# servo_1.net
KiCad netlist of a schematic drawn in EAGLE
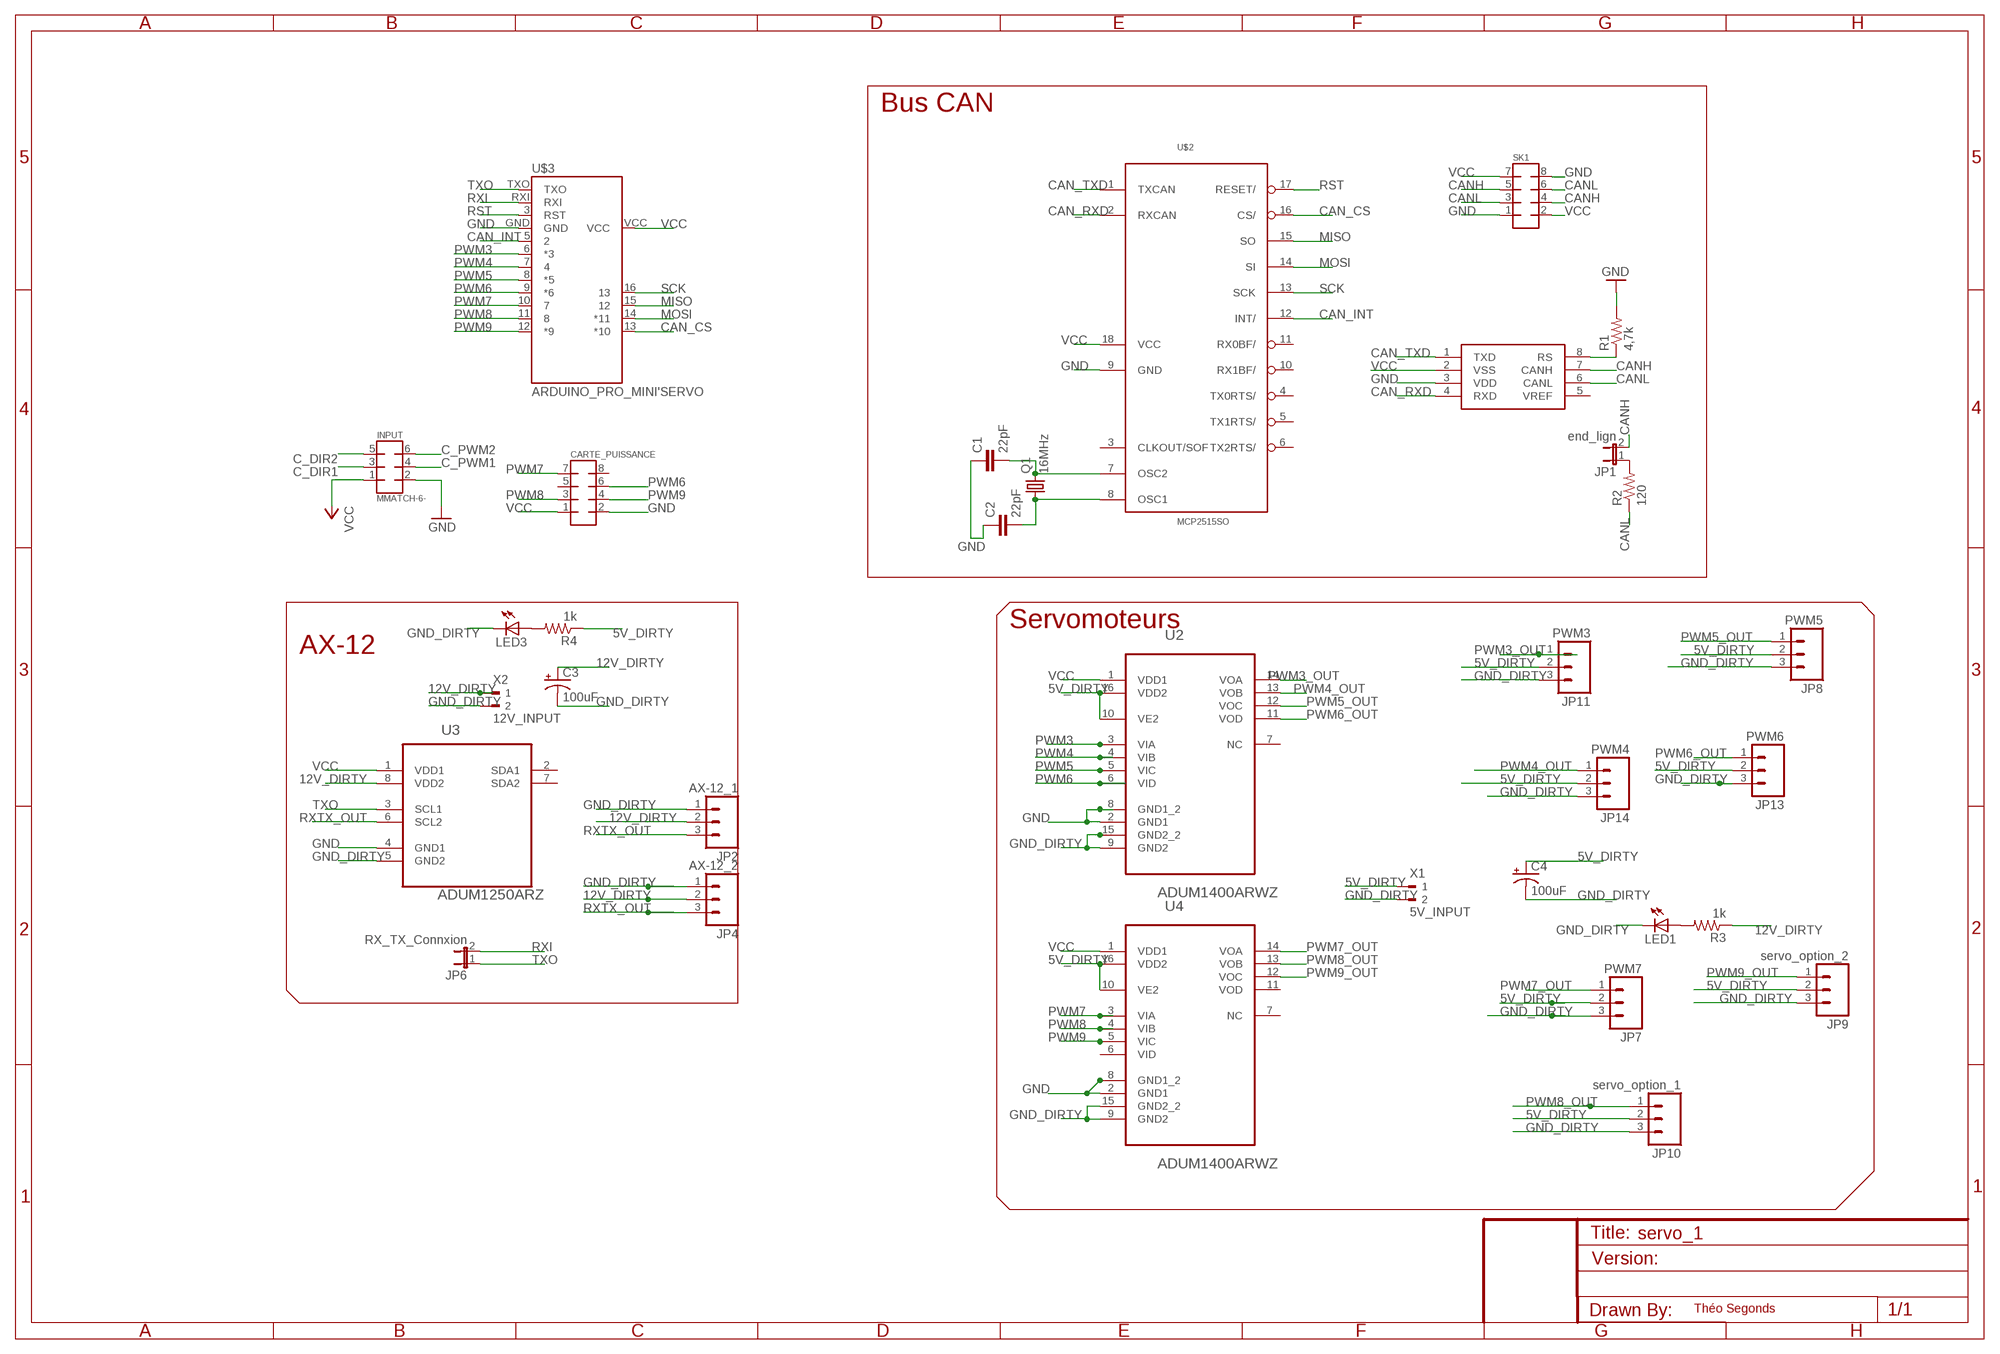
[diagram p0: schematic, sheet 1]

(export (version "E")
  (design (tool "Eeschema 10.0.6"))
  (components
    (comp (ref "C1")
      (value "22pF")
      (footprint "eagle-import:0805")
      (fields (field (name "MF") "AVX") (field (name "MPN") "08055A220JAT2A"))
      (libsource (lib "eagle-import") (part "CAP0805"))
    )
    (comp (ref "C2")
      (value "22pF")
      (footprint "eagle-import:0805")
      (fields (field (name "MF") "AVX") (field (name "MPN") "08055A220JAT2A"))
      (libsource (lib "eagle-import") (part "CAP0805"))
    )
    (comp (ref "C3")
      (value "100uF")
      (footprint "eagle-import:CPOL-RADIAL-100UF-25V")
      (fields (field (name "MF") "RUBYCON") (field (name "MPN") "100TXW100MEFC8X30"))
      (libsource (lib "eagle-import") (part "CAP_POLPTH1"))
    )
    (comp (ref "C4")
      (value "100uF")
      (footprint "eagle-import:CPOL-RADIAL-100UF-25V")
      (fields (field (name "MF") "RUBYCON") (field (name "MPN") "100TXW100MEFC8X30"))
      (libsource (lib "eagle-import") (part "CAP_POLPTH1"))
    )
    (comp (ref "CARTE_PUISSANCE")
      (value "MMATCH-8-PTH")
      (footprint "eagle-import:AMP-215079-8")
      (libsource (lib "eagle-import") (part "MMATCH-8-PTH"))
    )
    (comp (ref "INPUT")
      (value "MMATCH-6-")
      (footprint "eagle-import:AMP-215079-6")
      (libsource (lib "eagle-import") (part "MMATCH-6-"))
    )
    (comp (ref "JP1")
      (value "end_lign")
      (footprint "eagle-import:1X02")
      (libsource (lib "eagle-import") (part "JUMPER-2PTH"))
    )
    (comp (ref "JP2")
      (value "AX-12_1")
      (footprint "eagle-import:MOLEX-1X3")
      (libsource (lib "eagle-import") (part "M03POLAR"))
    )
    (comp (ref "JP4")
      (value "AX-12_2")
      (footprint "eagle-import:MOLEX-1X3")
      (libsource (lib "eagle-import") (part "M03POLAR"))
    )
    (comp (ref "JP6")
      (value "RX_TX_Connxion")
      (footprint "eagle-import:1X02")
      (libsource (lib "eagle-import") (part "JUMPER-2PTH"))
    )
    (comp (ref "JP7")
      (value "PWM7")
      (footprint "eagle-import:1X03")
      (libsource (lib "eagle-import") (part "M03PTH"))
    )
    (comp (ref "JP8")
      (value "PWM5")
      (footprint "eagle-import:1X03")
      (libsource (lib "eagle-import") (part "M03PTH"))
    )
    (comp (ref "JP9")
      (value "servo_option_2")
      (footprint "eagle-import:1X03")
      (libsource (lib "eagle-import") (part "M03PTH"))
    )
    (comp (ref "JP10")
      (value "servo_option_1")
      (footprint "eagle-import:1X03")
      (libsource (lib "eagle-import") (part "M03PTH"))
    )
    (comp (ref "JP11")
      (value "PWM3")
      (footprint "eagle-import:1X03")
      (libsource (lib "eagle-import") (part "M03PTH"))
    )
    (comp (ref "JP13")
      (value "PWM6")
      (footprint "eagle-import:1X03")
      (libsource (lib "eagle-import") (part "M03PTH"))
    )
    (comp (ref "JP14")
      (value "PWM4")
      (footprint "eagle-import:1X03")
      (libsource (lib "eagle-import") (part "M03PTH"))
    )
    (comp (ref "LED1")
      (value "LEDCHIPLED_0805")
      (footprint "eagle-import:CHIPLED_0805")
      (libsource (lib "eagle-import") (part "LEDCHIPLED_0805"))
    )
    (comp (ref "LED3")
      (value "LEDCHIPLED_0805")
      (footprint "eagle-import:CHIPLED_0805")
      (libsource (lib "eagle-import") (part "LEDCHIPLED_0805"))
    )
    (comp (ref "Q1")
      (value "16MHz")
      (footprint "eagle-import:HC49_S")
      (fields (field (name "MF") "MULTICOMP") (field (name "MPN") "HC49SM-3.6864-30-50-60-16-ATF"))
      (libsource (lib "eagle-import") (part "CRYSTALHC49S"))
    )
    (comp (ref "R1")
      (value "4,7k")
      (footprint "eagle-import:0805")
      (libsource (lib "eagle-import") (part "RESISTOR0805-RES"))
    )
    (comp (ref "R2")
      (value "120")
      (footprint "eagle-import:0805")
      (libsource (lib "eagle-import") (part "RESISTOR0805-RES"))
    )
    (comp (ref "R3")
      (value "1k")
      (footprint "eagle-import:0805")
      (libsource (lib "eagle-import") (part "RESISTOR0805-RES"))
    )
    (comp (ref "R4")
      (value "1k")
      (footprint "eagle-import:0805")
      (libsource (lib "eagle-import") (part "RESISTOR0805-RES"))
    )
    (comp (ref "SK1")
      (value "MMATCH-8-PTH")
      (footprint "eagle-import:AMP-215079-8")
      (libsource (lib "eagle-import") (part "MMATCH-8-PTH"))
    )
    (comp (ref "U$2")
      (value "MCP2515SO")
      (footprint "eagle-import:SO18L")
      (libsource (lib "eagle-import") (part "MCP2515SO"))
    )
    (comp (ref "U$3")
      (value "ARDUINO_PRO_MINI'SERVO")
      (footprint "eagle-import:ARDUINO_PRO_MINI")
      (libsource (lib "eagle-import") (part "ARDUINO_PRO_MINI'SERVO"))
    )
    (comp (ref "U1")
      (value "MCP2551")
      (footprint "eagle-import:SO08")
      (fields (field (name "MF") "MICROCHIP") (field (name "MPN") "MCP2551-I/SN..."))
      (libsource (lib "eagle-import") (part "MCP2551"))
    )
    (comp (ref "U2")
      (value "ADUM1400ARWZ")
      (footprint "eagle-import:SOIC127P1032X265-16N")
      (fields (field (name "MF") "ANALOG DEVICES"))
      (libsource (lib "eagle-import") (part "ADUM1400ARWZ"))
    )
    (comp (ref "U3")
      (value "ADUM1250ARZ")
      (footprint "eagle-import:SOIC127P600X175-8N")
      (fields (field (name "MF") "ANALOG DEVICES"))
      (libsource (lib "eagle-import") (part "ADUM1250ARZ"))
    )
    (comp (ref "U4")
      (value "ADUM1400ARWZ")
      (footprint "eagle-import:SOIC127P1032X265-16N")
      (fields (field (name "MF") "ANALOG DEVICES"))
      (libsource (lib "eagle-import") (part "ADUM1400ARWZ"))
    )
    (comp (ref "X1")
      (value "5V_INPUT")
      (footprint "eagle-import:90-2")
      (libsource (lib "eagle-import") (part "90-2"))
    )
    (comp (ref "X2")
      (value "12V_INPUT")
      (footprint "eagle-import:90-2")
      (libsource (lib "eagle-import") (part "90-2"))
    )
  )
  (nets
    (net (code "1") (name "/5V_DIRTY") (class "Default")
      (node (ref "C4") (pin "1") (pinfunction "+_1") (pintype "passive"))
      (node (ref "JP10") (pin "2") (pinfunction "2_2") (pintype "passive"))
      (node (ref "JP11") (pin "2") (pinfunction "2_2") (pintype "passive"))
      (node (ref "JP13") (pin "2") (pinfunction "2_2") (pintype "passive"))
      (node (ref "JP14") (pin "2") (pinfunction "2_2") (pintype "passive"))
      (node (ref "JP7") (pin "2") (pinfunction "2_2") (pintype "passive"))
      (node (ref "JP8") (pin "2") (pinfunction "2_2") (pintype "passive"))
      (node (ref "JP9") (pin "2") (pinfunction "2_2") (pintype "passive"))
      (node (ref "R4") (pin "1") (pinfunction "1_1") (pintype "passive"))
      (node (ref "U2") (pin "10") (pinfunction "VE2_10") (pintype "input"))
      (node (ref "U2") (pin "16") (pinfunction "VDD2_16") (pintype "power_in"))
      (node (ref "U4") (pin "10") (pinfunction "VE2_10") (pintype "input"))
      (node (ref "U4") (pin "16") (pinfunction "VDD2_16") (pintype "power_in"))
      (node (ref "X1") (pin "1") (pinfunction "1_1") (pintype "passive"))
    )
    (net (code "2") (name "/12V_DIRTY") (class "Default")
      (node (ref "C3") (pin "1") (pinfunction "+_1") (pintype "passive"))
      (node (ref "JP2") (pin "2") (pinfunction "2_2") (pintype "passive"))
      (node (ref "JP4") (pin "2") (pinfunction "2_2") (pintype "passive"))
      (node (ref "R3") (pin "1") (pinfunction "1_1") (pintype "passive"))
      (node (ref "U3") (pin "8") (pinfunction "VDD2_8") (pintype "power_in"))
      (node (ref "X2") (pin "1") (pinfunction "1_1") (pintype "passive"))
    )
    (net (code "3") (name "/CANH") (class "Default")
      (node (ref "JP1") (pin "2") (pinfunction "2_2") (pintype "passive"))
      (node (ref "SK1") (pin "4") (pinfunction "4_4") (pintype "bidirectional"))
      (node (ref "SK1") (pin "5") (pinfunction "5_5") (pintype "bidirectional"))
      (node (ref "U1") (pin "7") (pinfunction "CANH_7") (pintype "bidirectional"))
    )
    (net (code "4") (name "/CANL") (class "Default")
      (node (ref "R2") (pin "1") (pinfunction "1_1") (pintype "passive"))
      (node (ref "SK1") (pin "3") (pinfunction "3_3") (pintype "bidirectional"))
      (node (ref "SK1") (pin "6") (pinfunction "6_6") (pintype "bidirectional"))
      (node (ref "U1") (pin "6") (pinfunction "CANL_6") (pintype "bidirectional"))
    )
    (net (code "5") (name "/CAN_CS") (class "Default")
      (node (ref "U$2") (pin "16") (pinfunction "CS/_16") (pintype "input"))
      (node (ref "U$3") (pin "13") (pinfunction "*10_13") (pintype "bidirectional"))
    )
    (net (code "6") (name "/CAN_INT") (class "Default")
      (node (ref "U$2") (pin "12") (pinfunction "INT/_12") (pintype "output"))
      (node (ref "U$3") (pin "5") (pinfunction "2_5") (pintype "bidirectional"))
    )
    (net (code "7") (name "/CAN_RXD") (class "Default")
      (node (ref "U$2") (pin "2") (pinfunction "RXCAN_2") (pintype "input"))
      (node (ref "U1") (pin "4") (pinfunction "RXD_4") (pintype "bidirectional"))
    )
    (net (code "8") (name "/CAN_TXD") (class "Default")
      (node (ref "U$2") (pin "1") (pinfunction "TXCAN_1") (pintype "output"))
      (node (ref "U1") (pin "1") (pinfunction "TXD_1") (pintype "bidirectional"))
    )
    (net (code "9") (name "/C_DIR1") (class "Default")
      (node (ref "INPUT") (pin "3") (pinfunction "5_3") (pintype "bidirectional"))
    )
    (net (code "10") (name "/C_DIR2") (class "Default")
      (node (ref "INPUT") (pin "5") (pinfunction "7_5") (pintype "bidirectional"))
    )
    (net (code "11") (name "/C_PWM1") (class "Default")
      (node (ref "INPUT") (pin "4") (pinfunction "6_4") (pintype "bidirectional"))
    )
    (net (code "12") (name "/C_PWM2") (class "Default")
      (node (ref "INPUT") (pin "6") (pinfunction "8_6") (pintype "bidirectional"))
    )
    (net (code "13") (name "/GND_DIRTY") (class "Default")
      (node (ref "C3") (pin "2") (pinfunction "-_2") (pintype "passive"))
      (node (ref "C4") (pin "2") (pinfunction "-_2") (pintype "passive"))
      (node (ref "JP10") (pin "3") (pinfunction "3_3") (pintype "passive"))
      (node (ref "JP11") (pin "3") (pinfunction "3_3") (pintype "passive"))
      (node (ref "JP13") (pin "3") (pinfunction "3_3") (pintype "passive"))
      (node (ref "JP14") (pin "3") (pinfunction "3_3") (pintype "passive"))
      (node (ref "JP2") (pin "1") (pinfunction "1_1") (pintype "passive"))
      (node (ref "JP4") (pin "1") (pinfunction "1_1") (pintype "passive"))
      (node (ref "JP7") (pin "3") (pinfunction "3_3") (pintype "passive"))
      (node (ref "JP8") (pin "3") (pinfunction "3_3") (pintype "passive"))
      (node (ref "JP9") (pin "3") (pinfunction "3_3") (pintype "passive"))
      (node (ref "LED1") (pin "C") (pinfunction "C_C") (pintype "passive"))
      (node (ref "LED3") (pin "C") (pinfunction "C_C") (pintype "passive"))
      (node (ref "U2") (pin "15") (pinfunction "GND2_2_15") (pintype "passive"))
      (node (ref "U2") (pin "9") (pinfunction "GND2_9") (pintype "passive"))
      (node (ref "U3") (pin "5") (pinfunction "GND2_5") (pintype "passive"))
      (node (ref "U4") (pin "15") (pinfunction "GND2_2_15") (pintype "passive"))
      (node (ref "U4") (pin "9") (pinfunction "GND2_9") (pintype "passive"))
      (node (ref "X1") (pin "2") (pinfunction "2_2") (pintype "passive"))
      (node (ref "X2") (pin "2") (pinfunction "2_2") (pintype "passive"))
    )
    (net (code "14") (name "/MISO") (class "Default")
      (node (ref "U$2") (pin "15") (pinfunction "SO_15") (pintype "output"))
      (node (ref "U$3") (pin "15") (pinfunction "12_15") (pintype "bidirectional"))
    )
    (net (code "15") (name "/MOSI") (class "Default")
      (node (ref "U$2") (pin "14") (pinfunction "SI_14") (pintype "input"))
      (node (ref "U$3") (pin "14") (pinfunction "*11_14") (pintype "bidirectional"))
    )
    (net (code "16") (name "/PWM3") (class "Default")
      (node (ref "U$3") (pin "6") (pinfunction "*3_6") (pintype "bidirectional"))
      (node (ref "U2") (pin "3") (pinfunction "VIA_3") (pintype "input"))
    )
    (net (code "17") (name "/PWM3_OUT") (class "Default")
      (node (ref "JP11") (pin "1") (pinfunction "1_1") (pintype "passive"))
      (node (ref "U2") (pin "14") (pinfunction "VOA_14") (pintype "output"))
    )
    (net (code "18") (name "/PWM4") (class "Default")
      (node (ref "U$3") (pin "7") (pinfunction "4_7") (pintype "bidirectional"))
      (node (ref "U2") (pin "4") (pinfunction "VIB_4") (pintype "input"))
    )
    (net (code "19") (name "/PWM4_OUT") (class "Default")
      (node (ref "JP14") (pin "1") (pinfunction "1_1") (pintype "passive"))
      (node (ref "U2") (pin "13") (pinfunction "VOB_13") (pintype "output"))
    )
    (net (code "20") (name "/PWM5") (class "Default")
      (node (ref "U$3") (pin "8") (pinfunction "*5_8") (pintype "bidirectional"))
      (node (ref "U2") (pin "5") (pinfunction "VIC_5") (pintype "input"))
    )
    (net (code "21") (name "/PWM5_OUT") (class "Default")
      (node (ref "JP8") (pin "1") (pinfunction "1_1") (pintype "passive"))
      (node (ref "U2") (pin "12") (pinfunction "VOC_12") (pintype "output"))
    )
    (net (code "22") (name "/PWM6") (class "Default")
      (node (ref "CARTE_PUISSANCE") (pin "6") (pinfunction "6_6") (pintype "bidirectional"))
      (node (ref "U$3") (pin "9") (pinfunction "*6_9") (pintype "bidirectional"))
      (node (ref "U2") (pin "6") (pinfunction "VID_6") (pintype "input"))
    )
    (net (code "23") (name "/PWM6_OUT") (class "Default")
      (node (ref "JP13") (pin "1") (pinfunction "1_1") (pintype "passive"))
      (node (ref "U2") (pin "11") (pinfunction "VOD_11") (pintype "output"))
    )
    (net (code "24") (name "/PWM7") (class "Default")
      (node (ref "CARTE_PUISSANCE") (pin "7") (pinfunction "7_7") (pintype "bidirectional"))
      (node (ref "U$3") (pin "10") (pinfunction "7_10") (pintype "bidirectional"))
      (node (ref "U4") (pin "3") (pinfunction "VIA_3") (pintype "input"))
    )
    (net (code "25") (name "/PWM7_OUT") (class "Default")
      (node (ref "JP7") (pin "1") (pinfunction "1_1") (pintype "passive"))
      (node (ref "U4") (pin "14") (pinfunction "VOA_14") (pintype "output"))
    )
    (net (code "26") (name "/PWM8") (class "Default")
      (node (ref "CARTE_PUISSANCE") (pin "3") (pinfunction "3_3") (pintype "bidirectional"))
      (node (ref "U$3") (pin "11") (pinfunction "8_11") (pintype "bidirectional"))
      (node (ref "U4") (pin "4") (pinfunction "VIB_4") (pintype "input"))
    )
    (net (code "27") (name "/PWM8_OUT") (class "Default")
      (node (ref "JP10") (pin "1") (pinfunction "1_1") (pintype "passive"))
      (node (ref "U4") (pin "13") (pinfunction "VOB_13") (pintype "output"))
    )
    (net (code "28") (name "/PWM9") (class "Default")
      (node (ref "CARTE_PUISSANCE") (pin "4") (pinfunction "4_4") (pintype "bidirectional"))
      (node (ref "U$3") (pin "12") (pinfunction "*9_12") (pintype "bidirectional"))
      (node (ref "U4") (pin "5") (pinfunction "VIC_5") (pintype "input"))
    )
    (net (code "29") (name "/PWM9_OUT") (class "Default")
      (node (ref "JP9") (pin "1") (pinfunction "1_1") (pintype "passive"))
      (node (ref "U4") (pin "12") (pinfunction "VOC_12") (pintype "output"))
    )
    (net (code "30") (name "/RST") (class "Default")
      (node (ref "U$2") (pin "17") (pinfunction "RESET/_17") (pintype "input"))
      (node (ref "U$3") (pin "3") (pinfunction "RST_3") (pintype "bidirectional"))
    )
    (net (code "31") (name "/RXI") (class "Default")
      (node (ref "JP6") (pin "2") (pinfunction "2_2") (pintype "passive"))
      (node (ref "U$3") (pin "RXI") (pinfunction "RXI_RXI") (pintype "bidirectional"))
    )
    (net (code "32") (name "/RXTX_OUT") (class "Default")
      (node (ref "JP2") (pin "3") (pinfunction "3_3") (pintype "passive"))
      (node (ref "JP4") (pin "3") (pinfunction "3_3") (pintype "passive"))
      (node (ref "U3") (pin "6") (pinfunction "SCL2_6") (pintype "input"))
    )
    (net (code "33") (name "/SCK") (class "Default")
      (node (ref "U$2") (pin "13") (pinfunction "SCK_13") (pintype "input"))
      (node (ref "U$3") (pin "16") (pinfunction "13_16") (pintype "bidirectional"))
    )
    (net (code "34") (name "/TXO") (class "Default")
      (node (ref "JP6") (pin "1") (pinfunction "1_1") (pintype "passive"))
      (node (ref "U$3") (pin "TXO") (pinfunction "TXO_TXO") (pintype "bidirectional"))
      (node (ref "U3") (pin "3") (pinfunction "SCL1_3") (pintype "input"))
    )
    (net (code "35") (name "GND") (class "Default")
      (node (ref "C1") (pin "1") (pinfunction "1_1") (pintype "passive"))
      (node (ref "C2") (pin "1") (pinfunction "1_1") (pintype "passive"))
      (node (ref "CARTE_PUISSANCE") (pin "2") (pinfunction "2_2") (pintype "bidirectional"))
      (node (ref "INPUT") (pin "2") (pinfunction "4_2") (pintype "bidirectional"))
      (node (ref "R1") (pin "2") (pinfunction "2_2") (pintype "passive"))
      (node (ref "SK1") (pin "1") (pinfunction "1_1") (pintype "bidirectional"))
      (node (ref "SK1") (pin "8") (pinfunction "8_8") (pintype "bidirectional"))
      (node (ref "U$2") (pin "9") (pinfunction "GND_9") (pintype "power_in"))
      (node (ref "U$3") (pin "GND") (pinfunction "GND_GND") (pintype "bidirectional"))
      (node (ref "U1") (pin "3") (pinfunction "VDD_3") (pintype "bidirectional"))
      (node (ref "U2") (pin "2") (pinfunction "GND1_2") (pintype "passive"))
      (node (ref "U2") (pin "8") (pinfunction "GND1_2_8") (pintype "passive"))
      (node (ref "U3") (pin "4") (pinfunction "GND1_4") (pintype "passive"))
      (node (ref "U4") (pin "2") (pinfunction "GND1_2") (pintype "passive"))
      (node (ref "U4") (pin "8") (pinfunction "GND1_2_8") (pintype "passive"))
    )
    (net (code "36") (name "Net-(JP1-Pad1)") (class "Default")
      (node (ref "JP1") (pin "1") (pinfunction "1_1") (pintype "passive"))
      (node (ref "R2") (pin "2") (pinfunction "2_2") (pintype "passive"))
    )
    (net (code "37") (name "Net-(LED1-PadA)") (class "Default")
      (node (ref "LED1") (pin "A") (pinfunction "A_A") (pintype "passive"))
      (node (ref "R3") (pin "2") (pinfunction "2_2") (pintype "passive"))
    )
    (net (code "38") (name "Net-(LED3-PadA)") (class "Default")
      (node (ref "LED3") (pin "A") (pinfunction "A_A") (pintype "passive"))
      (node (ref "R4") (pin "2") (pinfunction "2_2") (pintype "passive"))
    )
    (net (code "39") (name "Net-(U$2-OSC1)") (class "Default")
      (node (ref "C2") (pin "2") (pinfunction "2_2") (pintype "passive"))
      (node (ref "Q1") (pin "1") (pinfunction "1_1") (pintype "passive"))
      (node (ref "U$2") (pin "8") (pinfunction "OSC1_8") (pintype "bidirectional"))
    )
    (net (code "40") (name "Net-(U$2-OSC2)") (class "Default")
      (node (ref "C1") (pin "2") (pinfunction "2_2") (pintype "passive"))
      (node (ref "Q1") (pin "2") (pinfunction "2_2") (pintype "passive"))
      (node (ref "U$2") (pin "7") (pinfunction "OSC2_7") (pintype "bidirectional"))
    )
    (net (code "41") (name "Net-(U1-RS)") (class "Default")
      (node (ref "R1") (pin "1") (pinfunction "1_1") (pintype "passive"))
      (node (ref "U1") (pin "8") (pinfunction "RS_8") (pintype "bidirectional"))
    )
    (net (code "42") (name "VCC") (class "Default")
      (node (ref "CARTE_PUISSANCE") (pin "1") (pinfunction "1_1") (pintype "bidirectional"))
      (node (ref "INPUT") (pin "1") (pinfunction "3_1") (pintype "bidirectional"))
      (node (ref "SK1") (pin "2") (pinfunction "2_2") (pintype "bidirectional"))
      (node (ref "SK1") (pin "7") (pinfunction "7_7") (pintype "bidirectional"))
      (node (ref "U$2") (pin "18") (pinfunction "VCC_18") (pintype "power_in"))
      (node (ref "U$3") (pin "VCC") (pinfunction "VCC_VCC") (pintype "bidirectional"))
      (node (ref "U1") (pin "2") (pinfunction "VSS_2") (pintype "bidirectional"))
      (node (ref "U2") (pin "1") (pinfunction "VDD1_1") (pintype "power_in"))
      (node (ref "U3") (pin "1") (pinfunction "VDD1_1") (pintype "power_in"))
      (node (ref "U4") (pin "1") (pinfunction "VDD1_1") (pintype "power_in"))
    )
    (net (code "43") (name "unconnected-(CARTE_PUISSANCE-Pad5)") (class "Default")
      (node (ref "CARTE_PUISSANCE") (pin "5") (pinfunction "5_5") (pintype "bidirectional"))
    )
    (net (code "44") (name "unconnected-(CARTE_PUISSANCE-Pad8)") (class "Default")
      (node (ref "CARTE_PUISSANCE") (pin "8") (pinfunction "8_8") (pintype "bidirectional"))
    )
    (net (code "45") (name "unconnected-(U$2-CLKOUT{slash}SOF-Pad3)") (class "Default")
      (node (ref "U$2") (pin "3") (pinfunction "CLKOUT/SOF_3") (pintype "bidirectional"))
    )
    (net (code "46") (name "unconnected-(U$2-RX0BF{slash}-Pad11)") (class "Default")
      (node (ref "U$2") (pin "11") (pinfunction "RX0BF/_11") (pintype "bidirectional"))
    )
    (net (code "47") (name "unconnected-(U$2-RX1BF{slash}-Pad10)") (class "Default")
      (node (ref "U$2") (pin "10") (pinfunction "RX1BF/_10") (pintype "bidirectional"))
    )
    (net (code "48") (name "unconnected-(U$2-TX0RTS{slash}-Pad4)") (class "Default")
      (node (ref "U$2") (pin "4") (pinfunction "TX0RTS/_4") (pintype "bidirectional"))
    )
    (net (code "49") (name "unconnected-(U$2-TX1RTS{slash}-Pad5)") (class "Default")
      (node (ref "U$2") (pin "5") (pinfunction "TX1RTS/_5") (pintype "bidirectional"))
    )
    (net (code "50") (name "unconnected-(U$2-TX2RTS{slash}-Pad6)") (class "Default")
      (node (ref "U$2") (pin "6") (pinfunction "TX2RTS/_6") (pintype "bidirectional"))
    )
    (net (code "51") (name "unconnected-(U1-VREF-Pad5)") (class "Default")
      (node (ref "U1") (pin "5") (pinfunction "VREF_5") (pintype "bidirectional"))
    )
    (net (code "52") (name "unconnected-(U2-NC-Pad7)") (class "Default")
      (node (ref "U2") (pin "7") (pinfunction "NC_7") (pintype "no_connect"))
    )
    (net (code "53") (name "unconnected-(U3-SDA1-Pad2)") (class "Default")
      (node (ref "U3") (pin "2") (pinfunction "SDA1_2") (pintype "bidirectional"))
    )
    (net (code "54") (name "unconnected-(U3-SDA2-Pad7)") (class "Default")
      (node (ref "U3") (pin "7") (pinfunction "SDA2_7") (pintype "bidirectional"))
    )
    (net (code "55") (name "unconnected-(U4-NC-Pad7)") (class "Default")
      (node (ref "U4") (pin "7") (pinfunction "NC_7") (pintype "no_connect"))
    )
    (net (code "56") (name "unconnected-(U4-VID-Pad6)") (class "Default")
      (node (ref "U4") (pin "6") (pinfunction "VID_6") (pintype "input"))
    )
    (net (code "57") (name "unconnected-(U4-VOD-Pad11)") (class "Default")
      (node (ref "U4") (pin "11") (pinfunction "VOD_11") (pintype "output"))
    )
  )
)
